# Test_Board.net
KiCad netlist of a schematic drawn in Altium Designer
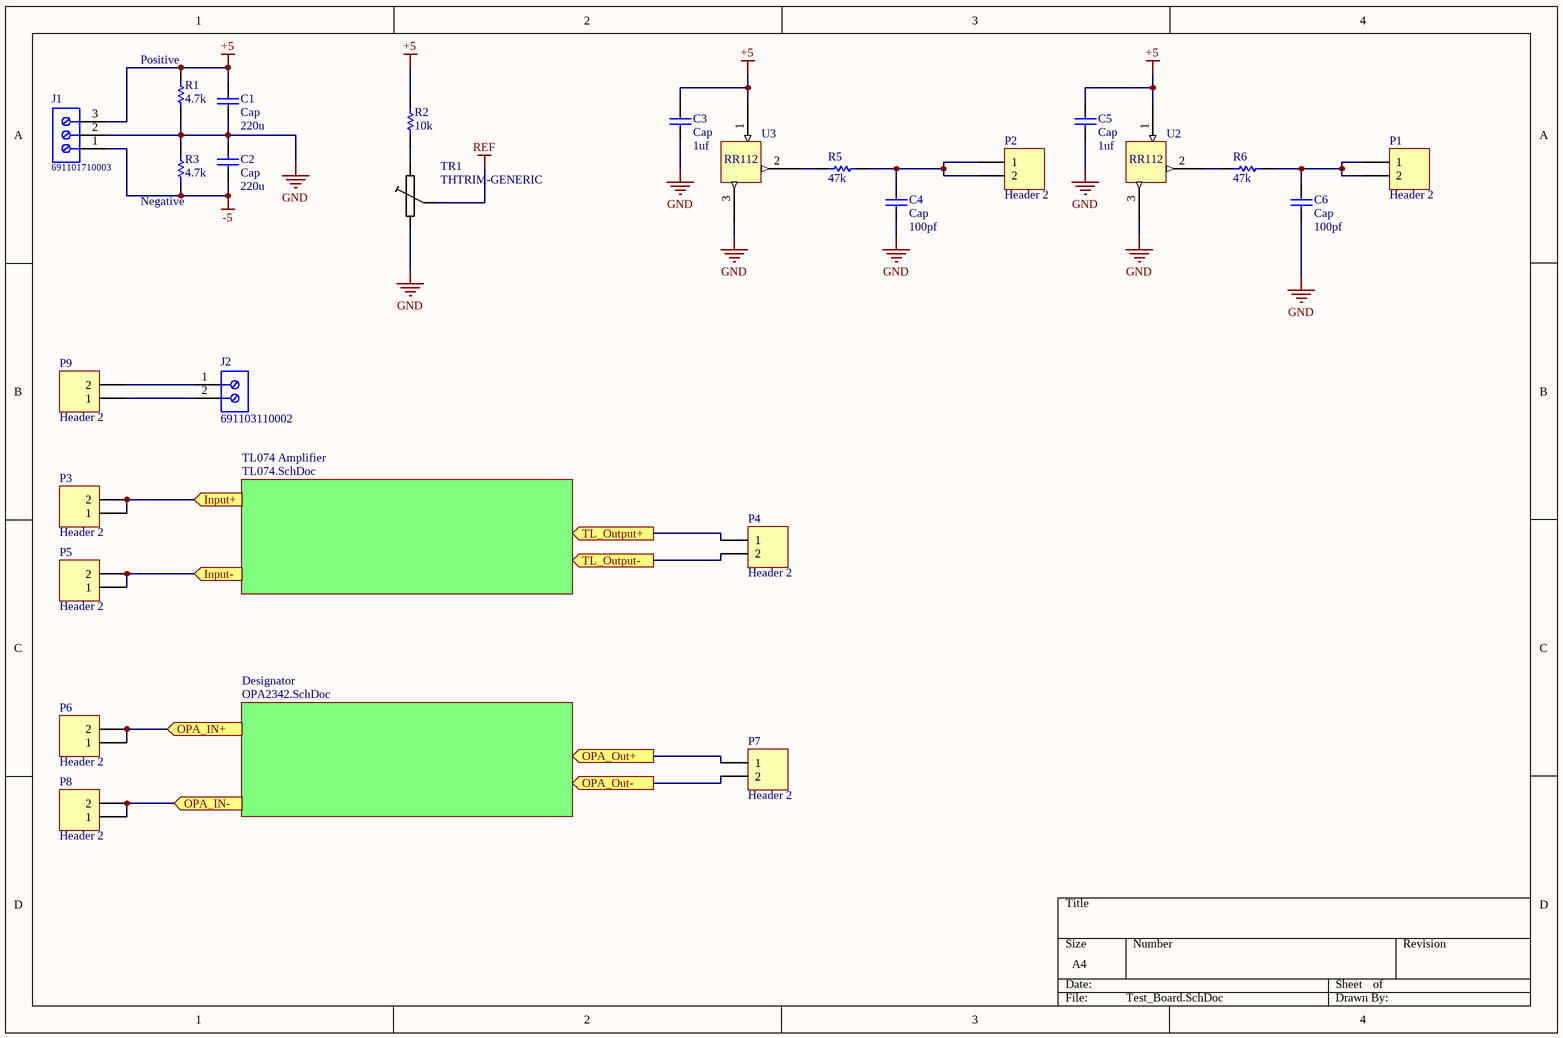
[diagram p0: Test_Board.SchDoc]

(export (version "E")
  (design (tool "Eeschema 10.0.6"))
  (components
    (comp (ref "C1")
      (value "Cap")
      (footprint "RAD-0.3")
      (description "Capacitor")
      (fields (field (name "ALTIUM_VALUE") "220u") (field (name "PUBLISHER") "Altium Limited"))
      (libsource (lib "Miscellaneous Devices") (part "Cap"))
    )
    (comp (ref "C2")
      (value "Cap")
      (footprint "C1206")
      (description "Capacitor")
      (fields (field (name "ALTIUM_VALUE") "220u") (field (name "PUBLISHER") "Altium Limited"))
      (libsource (lib "Miscellaneous Devices") (part "Cap"))
    )
    (comp (ref "C3")
      (value "Cap")
      (footprint "C1206")
      (description "Capacitor")
      (fields (field (name "ALTIUM_VALUE") "1uf") (field (name "PUBLISHER") "Altium Limited"))
      (libsource (lib "Miscellaneous Devices") (part "Cap"))
    )
    (comp (ref "C4")
      (value "Cap")
      (footprint "C1206")
      (description "Capacitor")
      (fields (field (name "ALTIUM_VALUE") "100pf") (field (name "PUBLISHER") "Altium Limited"))
      (libsource (lib "Miscellaneous Devices") (part "Cap"))
    )
    (comp (ref "C5")
      (value "Cap")
      (footprint "C1206")
      (description "Capacitor")
      (fields (field (name "ALTIUM_VALUE") "1uf") (field (name "PUBLISHER") "Altium Limited"))
      (libsource (lib "Miscellaneous Devices") (part "Cap"))
    )
    (comp (ref "C6")
      (value "Cap")
      (footprint "C1206")
      (description "Capacitor")
      (fields (field (name "ALTIUM_VALUE") "100pf") (field (name "PUBLISHER") "Altium Limited"))
      (libsource (lib "Miscellaneous Devices") (part "Cap"))
    )
    (comp (ref "J1")
      (value "691101710003")
      (footprint "691101710003")
      (description "Series 101 - 5.00 mm Horizontal Entry Modular with Pressure Clamp WR-TBL, 3 pin")
      (fields (field (name "MANUFACTURER") "Wurth Elektronik") (field (name "PUBLISHER") "WurthElektronik"))
      (libsource (lib "Altium Content Vault") (part "WE-CN-1P-F-TB3"))
    )
    (comp (ref "J2")
      (value "691103110002")
      (footprint "691103110002")
      (description "Series 1031 - 3.50 mm Horizontal Entry Modular with Pressure Clamp WR-TBL, 2 pin")
      (fields (field (name "MANUFACTURER") "Wurth Elektronik") (field (name "PUBLISHER") "WurthElektronik"))
      (libsource (lib "Altium Content Vault") (part "WE-CN-1P-F-TB2"))
    )
    (comp (ref "P1")
      (value "Header 2")
      (footprint "HDR1X2")
      (description "Header, 2-Pin")
      (fields (field (name "PUBLISHER") "Altium Limited"))
      (libsource (lib "Miscellaneous Connectors") (part "Header 2"))
    )
    (comp (ref "P2")
      (value "Header 2")
      (footprint "HDR1X2")
      (description "Header, 2-Pin")
      (fields (field (name "PUBLISHER") "Altium Limited"))
      (libsource (lib "Miscellaneous Connectors") (part "Header 2"))
    )
    (comp (ref "P3")
      (value "Header 2")
      (footprint "HDR1X2")
      (description "Header, 2-Pin")
      (fields (field (name "PUBLISHER") "Altium Limited"))
      (libsource (lib "") (part "Header 2_1"))
    )
    (comp (ref "P4")
      (value "Header 2")
      (footprint "HDR1X2")
      (description "Header, 2-Pin")
      (fields (field (name "PUBLISHER") "Altium Limited"))
      (libsource (lib "Miscellaneous Connectors") (part "Header 2"))
    )
    (comp (ref "P5")
      (value "Header 2")
      (footprint "HDR1X2")
      (description "Header, 2-Pin")
      (fields (field (name "PUBLISHER") "Altium Limited"))
      (libsource (lib "") (part "Header 2_1"))
    )
    (comp (ref "P6")
      (value "Header 2")
      (footprint "HDR1X2")
      (description "Header, 2-Pin")
      (fields (field (name "PUBLISHER") "Altium Limited"))
      (libsource (lib "") (part "Header 2_1"))
    )
    (comp (ref "P7")
      (value "Header 2")
      (footprint "HDR1X2")
      (description "Header, 2-Pin")
      (fields (field (name "PUBLISHER") "Altium Limited"))
      (libsource (lib "Miscellaneous Connectors") (part "Header 2"))
    )
    (comp (ref "P8")
      (value "Header 2")
      (footprint "HDR1X2")
      (description "Header, 2-Pin")
      (fields (field (name "PUBLISHER") "Altium Limited"))
      (libsource (lib "") (part "Header 2_1"))
    )
    (comp (ref "P9")
      (value "Header 2")
      (footprint "HDR1X2")
      (description "Header, 2-Pin")
      (fields (field (name "PUBLISHER") "Altium Limited"))
      (libsource (lib "") (part "Header 2_1"))
    )
    (comp (ref "R1")
      (value "4.7k")
      (footprint "RESC3216X89X51LL25T25")
      (fields (field (name "PART NUMBER") "WSLP1206R0500FEA") (field (name "MANUFACTURER") "Vishay Dale"))
      (libsource (lib "Altium Content Vault") (part "RES"))
    )
    (comp (ref "R2")
      (value "10k")
      (footprint "RESC3216X89X51LL25T25")
      (fields (field (name "PART NUMBER") "WSLP1206R0500FEA") (field (name "MANUFACTURER") "Vishay Dale"))
      (libsource (lib "Altium Content Vault") (part "RES"))
    )
    (comp (ref "R3")
      (value "4.7k")
      (footprint "RESC3216X89X51LL25T25")
      (fields (field (name "PART NUMBER") "WSLP1206R0500FEA") (field (name "MANUFACTURER") "Vishay Dale"))
      (libsource (lib "Altium Content Vault") (part "RES"))
    )
    (comp (ref "R5")
      (value "47k")
      (footprint "RESC3216X89X51LL25T25")
      (fields (field (name "PART NUMBER") "WSLP1206R0500FEA") (field (name "MANUFACTURER") "Vishay Dale"))
      (libsource (lib "Altium Content Vault") (part "RES"))
    )
    (comp (ref "R6")
      (value "47k")
      (footprint "RESC3216X89X51LL25T25")
      (fields (field (name "PART NUMBER") "WSLP1206R0500FEA") (field (name "MANUFACTURER") "Vishay Dale"))
      (libsource (lib "Altium Content Vault") (part "RES"))
    )
    (comp (ref "TR1")
      (value "THTRIM-GENERIC")
      (footprint "TRIMMER-MT")
      (description "TRIMMABLE RESISTOR")
      (libsource (lib "vh_altium_library") (part "THTRIM-GENERIC"))
    )
    (comp (ref "U2")
      (value "RR112-1G42-531")
      (footprint "SOT145P280X140-3N")
      (description "TMR Sensor")
      (libsource (lib "Irfaan's Workspace") (part "RR112-1G42-531-Symbol-1"))
    )
    (comp (ref "U3")
      (value "RR112-1G42-531")
      (footprint "SOT145P280X140-3N")
      (description "TMR Sensor")
      (libsource (lib "Irfaan's Workspace") (part "RR112-1G42-531-Symbol-1"))
    )
  )
  (nets
    (net (code "1") (name "+5") (class "Default")
      (node (ref "C1") (pin "1") (pinfunction "1_1") (pintype "passive"))
      (node (ref "C3") (pin "1") (pinfunction "1_1") (pintype "passive"))
      (node (ref "C5") (pin "1") (pinfunction "1_1") (pintype "passive"))
      (node (ref "J1") (pin "3") (pinfunction "3_3") (pintype "passive"))
      (node (ref "R1") (pin "2") (pinfunction "2_2") (pintype "passive"))
      (node (ref "R2") (pin "2") (pinfunction "2_2") (pintype "passive"))
      (node (ref "U2") (pin "1") (pinfunction "Vdd_1") (pintype "input"))
      (node (ref "U3") (pin "1") (pinfunction "Vdd_1") (pintype "input"))
    )
    (net (code "2") (name "-5") (class "Default")
      (node (ref "C2") (pin "2") (pinfunction "2_2") (pintype "passive"))
      (node (ref "J1") (pin "1") (pinfunction "1_1") (pintype "passive"))
      (node (ref "R3") (pin "1") (pinfunction "1_1") (pintype "passive"))
    )
    (net (code "3") (name "/Input+") (class "Default")
      (node (ref "P3") (pin "1") (pinfunction "1_1") (pintype "passive"))
      (node (ref "P3") (pin "2") (pinfunction "2_2") (pintype "passive"))
    )
    (net (code "4") (name "/Input-") (class "Default")
      (node (ref "P5") (pin "1") (pinfunction "1_1") (pintype "passive"))
      (node (ref "P5") (pin "2") (pinfunction "2_2") (pintype "passive"))
    )
    (net (code "5") (name "/OPA_IN+") (class "Default")
      (node (ref "P6") (pin "1") (pinfunction "1_1") (pintype "passive"))
      (node (ref "P6") (pin "2") (pinfunction "2_2") (pintype "passive"))
    )
    (net (code "6") (name "/OPA_IN-") (class "Default")
      (node (ref "P8") (pin "1") (pinfunction "1_1") (pintype "passive"))
      (node (ref "P8") (pin "2") (pinfunction "2_2") (pintype "passive"))
    )
    (net (code "7") (name "/OPA_Out+") (class "Default")
      (node (ref "P7") (pin "1") (pinfunction "1_1") (pintype "passive"))
    )
    (net (code "8") (name "/OPA_Out-") (class "Default")
      (node (ref "P7") (pin "2") (pinfunction "2_2") (pintype "passive"))
    )
    (net (code "9") (name "/TL_Output+") (class "Default")
      (node (ref "P4") (pin "1") (pinfunction "1_1") (pintype "passive"))
    )
    (net (code "10") (name "/TL_Output-") (class "Default")
      (node (ref "P4") (pin "2") (pinfunction "2_2") (pintype "passive"))
    )
    (net (code "11") (name "GND") (class "Default")
      (node (ref "C1") (pin "2") (pinfunction "2_2") (pintype "passive"))
      (node (ref "C2") (pin "1") (pinfunction "1_1") (pintype "passive"))
      (node (ref "C3") (pin "2") (pinfunction "2_2") (pintype "passive"))
      (node (ref "C4") (pin "2") (pinfunction "2_2") (pintype "passive"))
      (node (ref "C5") (pin "2") (pinfunction "2_2") (pintype "passive"))
      (node (ref "C6") (pin "2") (pinfunction "2_2") (pintype "passive"))
      (node (ref "J1") (pin "2") (pinfunction "2_2") (pintype "passive"))
      (node (ref "R1") (pin "1") (pinfunction "1_1") (pintype "passive"))
      (node (ref "R3") (pin "2") (pinfunction "2_2") (pintype "passive"))
      (node (ref "TR1") (pin "1") (pinfunction "1_1") (pintype "passive"))
      (node (ref "U2") (pin "3") (pinfunction "GND_3") (pintype "output"))
      (node (ref "U3") (pin "3") (pinfunction "GND_3") (pintype "output"))
    )
    (net (code "12") (name "Net-(C4-Pad1)") (class "Default")
      (node (ref "C4") (pin "1") (pinfunction "1_1") (pintype "passive"))
      (node (ref "P2") (pin "1") (pinfunction "1_1") (pintype "passive"))
      (node (ref "P2") (pin "2") (pinfunction "2_2") (pintype "passive"))
      (node (ref "R5") (pin "1") (pinfunction "1_1") (pintype "passive"))
    )
    (net (code "13") (name "Net-(C6-Pad1)") (class "Default")
      (node (ref "C6") (pin "1") (pinfunction "1_1") (pintype "passive"))
      (node (ref "P1") (pin "1") (pinfunction "1_1") (pintype "passive"))
      (node (ref "P1") (pin "2") (pinfunction "2_2") (pintype "passive"))
      (node (ref "R6") (pin "1") (pinfunction "1_1") (pintype "passive"))
    )
    (net (code "14") (name "Net-(J2-Pad1)") (class "Default")
      (node (ref "J2") (pin "1") (pinfunction "1_1") (pintype "passive"))
      (node (ref "P9") (pin "2") (pinfunction "2_2") (pintype "passive"))
    )
    (net (code "15") (name "Net-(J2-Pad2)") (class "Default")
      (node (ref "J2") (pin "2") (pinfunction "2_2") (pintype "passive"))
      (node (ref "P9") (pin "1") (pinfunction "1_1") (pintype "passive"))
    )
    (net (code "16") (name "Net-(R2-Pad1)") (class "Default")
      (node (ref "R2") (pin "1") (pinfunction "1_1") (pintype "passive"))
      (node (ref "TR1") (pin "2") (pinfunction "2_2") (pintype "passive"))
    )
    (net (code "17") (name "Net-(U2-Output)") (class "Default")
      (node (ref "R6") (pin "2") (pinfunction "2_2") (pintype "passive"))
      (node (ref "U2") (pin "2") (pinfunction "Output_2") (pintype "output"))
    )
    (net (code "18") (name "Net-(U3-Output)") (class "Default")
      (node (ref "R5") (pin "2") (pinfunction "2_2") (pintype "passive"))
      (node (ref "U3") (pin "2") (pinfunction "Output_2") (pintype "output"))
    )
    (net (code "19") (name "REF") (class "Default")
      (node (ref "TR1") (pin "W") (pinfunction "W_W") (pintype "passive"))
    )
  )
)
